# Sheet1.net
KiCad netlist of a schematic drawn in Altium Designer
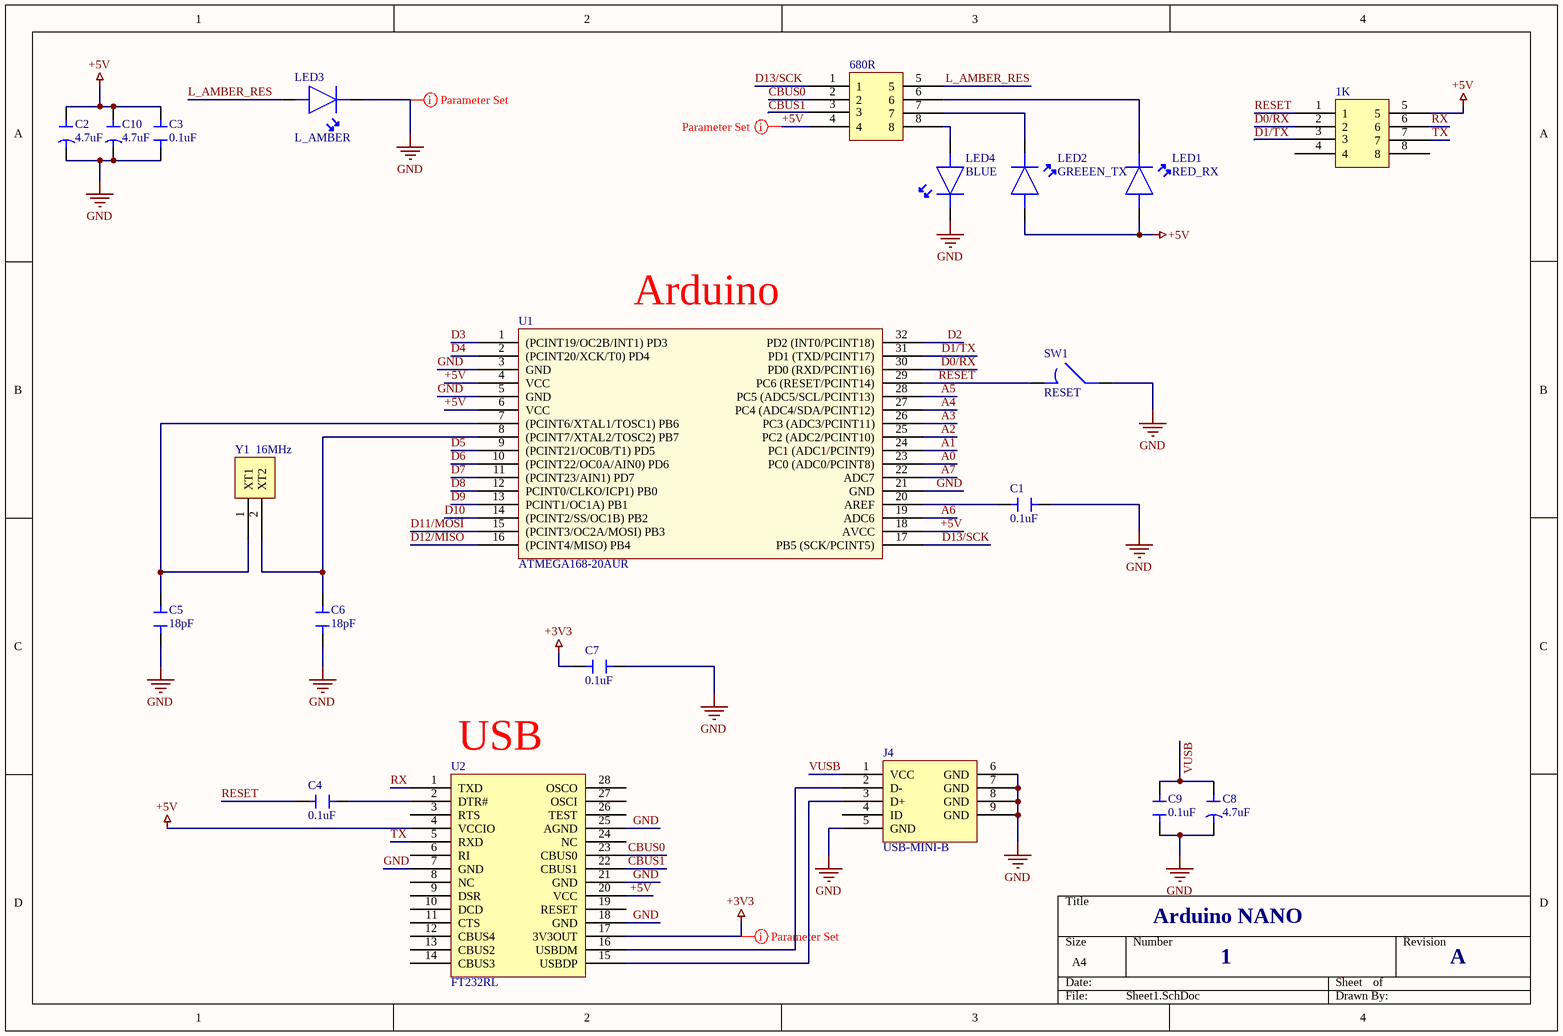
[diagram p0: Sheet1.SchDoc]

(export (version "E")
  (design (tool "Eeschema 10.0.6"))
  (components
    (comp (ref "1K")
      (value "YC164-JR-071KL")
      (footprint "Quad8 RES ARRAY")
      (description "Res Thick Film Array 1KOhm 5% 200ppm/C ISOL Epoxy 8-Pin 1206(4 X 0603) Convex SMD T/R")
      (fields (field (name "MANUFACTURER") "Yageo") (field (name "TOLERANCE") "5%"))
      (libsource (lib "Schlib1") (part "YC164-JR-071KL"))
    )
    (comp (ref "680R")
      (value "YC164-JR-07680RL")
      (footprint "Quad8 RES ARRAY")
      (description "Res Thick Film Array 680 Ohm 5% 200ppm/ C ISOL Molded 8-Pin 1206(4 X 0603) Convex SMD Paper T/R")
      (fields (field (name "MANUFACTURER") "Yageo"))
      (libsource (lib "Schlib1") (part "YC164-JR-07680RL"))
    )
    (comp (ref "C1")
      (value "0.1uF")
      (footprint "Capacitor 0805")
      (libsource (lib "Schlib1") (part "CL21F104ZBCNNNC"))
    )
    (comp (ref "C2")
      (value "4.7uF")
      (footprint "Tant 7343-43")
      (description "Cap Tant Solid 4.7uF 50V D CASE 10% (7.3 X 4.3 X 2.8mm) SMD 7343-31 1.2 Ohm 125 C T/R")
      (fields
        (field (name "MANUFACTURER") "Vishay Sprague")
        (field (name "MANUFACTURER PART NUMBER") "293D475X9050D2TE3")
      )
      (libsource (lib "Schlib1") (part "293D475X9050D2TE3"))
    )
    (comp (ref "C3")
      (value "0.1uF")
      (footprint "Capacitor 0805")
      (description "Multilayer Ceramic Capacitor, 18 pF, 16 V, ± 2%, C0G (NP0), 0805 [2012 Metric]")
      (fields
        (field (name "MANUFACTURER") "Vishay Vitramon")
        (field (name "MANUFACTURER PART NUMBER") "VJ0805A180GXJCW1BC")
      )
      (libsource (lib "Schlib1") (part "VJ0805A180GXJCW1BC"))
    )
    (comp (ref "C4")
      (value "0.1uF")
      (footprint "Capacitor 0805")
      (description "Multilayer Ceramic Capacitor, 18 pF, 16 V, ± 2%, C0G (NP0), 0805 [2012 Metric]")
      (fields
        (field (name "MANUFACTURER") "Vishay Vitramon")
        (field (name "MANUFACTURER PART NUMBER") "VJ0805A180GXJCW1BC")
      )
      (libsource (lib "Schlib1") (part "VJ0805A180GXJCW1BC"))
    )
    (comp (ref "C5")
      (value "18pF")
      (footprint "Capacitor 0805")
      (description "Multilayer Ceramic Capacitor, 18 pF, 16 V, ± 2%, C0G (NP0), 0805 [2012 Metric]")
      (fields
        (field (name "MANUFACTURER") "Vishay Vitramon")
        (field (name "MANUFACTURER PART NUMBER") "VJ0805A180GXJCW1BC")
      )
      (libsource (lib "Schlib1") (part "VJ0805A180GXJCW1BC"))
    )
    (comp (ref "C6")
      (value "18pF")
      (footprint "Capacitor 0805")
      (description "Multilayer Ceramic Capacitor, 18 pF, 16 V, ± 2%, C0G (NP0), 0805 [2012 Metric]")
      (fields
        (field (name "MANUFACTURER") "Vishay Vitramon")
        (field (name "MANUFACTURER PART NUMBER") "VJ0805A180GXJCW1BC")
      )
      (libsource (lib "Schlib1") (part "VJ0805A180GXJCW1BC"))
    )
    (comp (ref "C7")
      (value "0.1uF")
      (footprint "Capacitor 0805")
      (description "Multilayer Ceramic Capacitor, 18 pF, 16 V, ± 2%, C0G (NP0), 0805 [2012 Metric]")
      (fields
        (field (name "MANUFACTURER") "Vishay Vitramon")
        (field (name "MANUFACTURER PART NUMBER") "VJ0805A180GXJCW1BC")
      )
      (libsource (lib "Schlib1") (part "VJ0805A180GXJCW1BC"))
    )
    (comp (ref "C8")
      (value "4.7uF")
      (footprint "Tant 7343-43")
      (description "Cap Tant Solid 4.7uF 50V D CASE 10% (7.3 X 4.3 X 2.8mm) SMD 7343-31 1.2 Ohm 125 C T/R")
      (fields
        (field (name "MANUFACTURER") "Vishay Sprague")
        (field (name "MANUFACTURER PART NUMBER") "293D475X9050D2TE3")
      )
      (libsource (lib "Schlib1") (part "293D475X9050D2TE3"))
    )
    (comp (ref "C9")
      (value "0.1uF")
      (footprint "Capacitor 0805")
      (description "Multilayer Ceramic Capacitor, 18 pF, 16 V, ± 2%, C0G (NP0), 0805 [2012 Metric]")
      (fields
        (field (name "MANUFACTURER") "Vishay Vitramon")
        (field (name "MANUFACTURER PART NUMBER") "VJ0805A180GXJCW1BC")
      )
      (libsource (lib "Schlib1") (part "VJ0805A180GXJCW1BC"))
    )
    (comp (ref "C10")
      (value "4.7uF")
      (footprint "Tant 7343-43")
      (description "Cap Tant Solid 4.7uF 50V D CASE 10% (7.3 X 4.3 X 2.8mm) SMD 7343-31 1.2 Ohm 125 C T/R")
      (fields
        (field (name "MANUFACTURER") "Vishay Sprague")
        (field (name "MANUFACTURER PART NUMBER") "293D475X9050D2TE3")
      )
      (libsource (lib "Schlib1") (part "293D475X9050D2TE3"))
    )
    (comp (ref "J4")
      (value "USB-MINI-B")
      (footprint "Mini B")
      (description "Conn Mini USB 2.0 Type B RCP 5 POS 0.8mm Solder RA SMD 5 Terminal 1 Port USB OTG T/R")
      (fields (field (name "MANUFACTURER") "Molex") (field (name "MANUFACTURER PART NUMBER") "67503-1020"))
      (libsource (lib "Schlib1") (part "67503-1020"))
    )
    (comp (ref "LED1")
      (value "RED_RX")
      (footprint "LED 0805")
      (libsource (lib "Schlib1") (part "APT2012SRCPRV"))
    )
    (comp (ref "LED2")
      (value "GREEEN_TX")
      (footprint "LED 0805")
      (libsource (lib "Schlib1") (part "APT2012SRCPRV"))
    )
    (comp (ref "LED3")
      (value "L_AMBER")
      (footprint "LED 0805")
      (libsource (lib "Schlib1") (part "APT2012SRCPRV"))
    )
    (comp (ref "LED4")
      (value "BLUE")
      (footprint "LED 0805")
      (libsource (lib "Schlib1") (part "APT2012SRCPRV"))
    )
    (comp (ref "SW1")
      (value "RESET")
      (footprint "PUSH BUTTON")
      (description "Switch Tactile N.O. SPST Round Button Gull Wing 0.05A 12VDC 1.5N SMD Embossed T/R")
      (fields (field (name "MANUFACTURER") "Omron") (field (name "MANUFACTURER PART NUMBER") "B3U-1000P"))
      (libsource (lib "Schlib1") (part "B3U-1000P"))
    )
    (comp (ref "U1")
      (value "ATMEGA168-20AUR")
      (footprint "TQFP")
      (description "MCU 8-bit ATmega AVR RISC 16KB Flash 3.3V/5V 32-Pin TQFP T/R - Tape and Reel")
      (fields (field (name "MANUFACTURER") "Microchip"))
      (libsource (lib "Schlib1") (part "ATMEGA168-20AUR"))
    )
    (comp (ref "U2")
      (value "FT232RL")
      (footprint "Quad28 FTDI")
      (description "IC USB FS SERIAL UART 28-SSOP")
      (fields (field (name "MANUFACTURER") "FTDI") (field (name "MANUFACTURER PART NUMBER") "FT232RL-REEL"))
      (libsource (lib "Schlib1") (part "FT232RL-REEL"))
    )
    (comp (ref "Y1")
      (value "16MHz")
      (footprint "TH XT")
      (description "Crystal 16MHz ±20ppm (Tol) ±50ppm (Stability) 18pF FUND 40Ohm 2-Pin HC-49/US Thru-Hole Bulk")
      (fields
        (field (name "MANUFACTURER") "Abracon")
        (field (name "MANUFACTURER PART NUMBER") "ABL-16.000MHZ-B2")
      )
      (libsource (lib "Schlib1") (part "ABL-16.000MHZ-B2"))
    )
  )
  (nets
    (net (code "1") (name "+3V3") (class "Default")
      (node (ref "C7") (pin "2") (pinfunction "2_2") (pintype "passive"))
      (node (ref "U2") (pin "17") (pinfunction "3V3OUT_17") (pintype "passive"))
    )
    (net (code "2") (name "+5V") (class "Default")
      (node (ref "1K") (pin "5") (pinfunction "5_5") (pintype "passive"))
      (node (ref "680R") (pin "4") (pinfunction "4_4") (pintype "passive"))
      (node (ref "C10") (pin "1") (pinfunction "1_1") (pintype "passive"))
      (node (ref "C2") (pin "1") (pinfunction "1_1") (pintype "passive"))
      (node (ref "C3") (pin "1") (pinfunction "1_1") (pintype "passive"))
      (node (ref "LED1") (pin "8") (pinfunction "8_8") (pintype "passive"))
      (node (ref "LED2") (pin "8") (pinfunction "8_8") (pintype "passive"))
      (node (ref "U1") (pin "18") (pinfunction "AVCC_18") (pintype "passive"))
      (node (ref "U1") (pin "4") (pinfunction "VCC_4") (pintype "passive"))
      (node (ref "U1") (pin "6") (pinfunction "VCC_6") (pintype "passive"))
      (node (ref "U2") (pin "20") (pinfunction "VCC_20") (pintype "passive"))
      (node (ref "U2") (pin "4") (pinfunction "VCCIO_4") (pintype "passive"))
    )
    (net (code "3") (name "/A0") (class "Default")
      (node (ref "U1") (pin "23") (pinfunction "PC0_(ADC0/PCINT8)_23") (pintype "passive"))
    )
    (net (code "4") (name "/A1") (class "Default")
      (node (ref "U1") (pin "24") (pinfunction "PC1_(ADC1/PCINT9)_24") (pintype "passive"))
    )
    (net (code "5") (name "/A2") (class "Default")
      (node (ref "U1") (pin "25") (pinfunction "PC2_(ADC2/PCINT10)_25") (pintype "passive"))
    )
    (net (code "6") (name "/A3") (class "Default")
      (node (ref "U1") (pin "26") (pinfunction "PC3_(ADC3/PCINT11)_26") (pintype "passive"))
    )
    (net (code "7") (name "/A4") (class "Default")
      (node (ref "U1") (pin "27") (pinfunction "PC4_(ADC4/SDA/PCINT12)_27") (pintype "passive"))
    )
    (net (code "8") (name "/A5") (class "Default")
      (node (ref "U1") (pin "28") (pinfunction "PC5_(ADC5/SCL/PCINT13)_28") (pintype "passive"))
    )
    (net (code "9") (name "/A6") (class "Default")
      (node (ref "U1") (pin "19") (pinfunction "ADC6_19") (pintype "passive"))
    )
    (net (code "10") (name "/A7") (class "Default")
      (node (ref "U1") (pin "22") (pinfunction "ADC7_22") (pintype "passive"))
    )
    (net (code "11") (name "/CBUS0") (class "Default")
      (node (ref "680R") (pin "2") (pinfunction "2_2") (pintype "passive"))
      (node (ref "U2") (pin "23") (pinfunction "CBUS0_23") (pintype "passive"))
    )
    (net (code "12") (name "/CBUS1") (class "Default")
      (node (ref "680R") (pin "3") (pinfunction "3_3") (pintype "passive"))
      (node (ref "U2") (pin "22") (pinfunction "CBUS1_22") (pintype "passive"))
    )
    (net (code "13") (name "/D0{slash}RX") (class "Default")
      (node (ref "1K") (pin "2") (pinfunction "2_2") (pintype "passive"))
      (node (ref "U1") (pin "30") (pinfunction "PD0_(RXD/PCINT16)_30") (pintype "passive"))
    )
    (net (code "14") (name "/D1{slash}TX") (class "Default")
      (node (ref "1K") (pin "3") (pinfunction "3_3") (pintype "passive"))
      (node (ref "U1") (pin "31") (pinfunction "PD1_(TXD/PCINT17)_31") (pintype "passive"))
    )
    (net (code "15") (name "/D2") (class "Default")
      (node (ref "U1") (pin "32") (pinfunction "PD2_(INT0/PCINT18)_32") (pintype "passive"))
    )
    (net (code "16") (name "/D3") (class "Default")
      (node (ref "U1") (pin "1") (pinfunction "(PCINT19/OC2B/INT1)_PD3_1") (pintype "passive"))
    )
    (net (code "17") (name "/D4") (class "Default")
      (node (ref "U1") (pin "2") (pinfunction "(PCINT20/XCK/T0)_PD4_2") (pintype "passive"))
    )
    (net (code "18") (name "/D5") (class "Default")
      (node (ref "U1") (pin "9") (pinfunction "(PCINT21/OC0B/T1)_PD5_9") (pintype "passive"))
    )
    (net (code "19") (name "/D6") (class "Default")
      (node (ref "U1") (pin "10") (pinfunction "(PCINT22/OC0A/AIN0)_PD6_10") (pintype "passive"))
    )
    (net (code "20") (name "/D7") (class "Default")
      (node (ref "U1") (pin "11") (pinfunction "(PCINT23/AIN1)_PD7_11") (pintype "passive"))
    )
    (net (code "21") (name "/D8") (class "Default")
      (node (ref "U1") (pin "12") (pinfunction "PCINT0/CLKO/ICP1)_PB0_12") (pintype "passive"))
    )
    (net (code "22") (name "/D9") (class "Default")
      (node (ref "U1") (pin "13") (pinfunction "PCINT1/OC1A)_PB1_13") (pintype "passive"))
    )
    (net (code "23") (name "/D10") (class "Default")
      (node (ref "U1") (pin "14") (pinfunction "(PCINT2/SS/OC1B)_PB2_14") (pintype "passive"))
    )
    (net (code "24") (name "/D11{slash}MOSI") (class "Default")
      (node (ref "U1") (pin "15") (pinfunction "(PCINT3/OC2A/MOSI)_PB3_15") (pintype "passive"))
    )
    (net (code "25") (name "/D12{slash}MISO") (class "Default")
      (node (ref "U1") (pin "16") (pinfunction "(PCINT4/MISO)_PB4_16") (pintype "passive"))
    )
    (net (code "26") (name "/D13{slash}SCK") (class "Default")
      (node (ref "680R") (pin "1") (pinfunction "1_1") (pintype "passive"))
      (node (ref "U1") (pin "17") (pinfunction "PB5_(SCK/PCINT5)_17") (pintype "passive"))
    )
    (net (code "27") (name "/L_AMBER_RES") (class "Default")
      (node (ref "680R") (pin "5") (pinfunction "5_5") (pintype "passive"))
      (node (ref "LED3") (pin "8") (pinfunction "8_8") (pintype "passive"))
    )
    (net (code "28") (name "/RESET") (class "Default")
      (node (ref "1K") (pin "1") (pinfunction "1_1") (pintype "passive"))
      (node (ref "C4") (pin "2") (pinfunction "2_2") (pintype "passive"))
      (node (ref "SW1") (pin "9") (pinfunction "9_9") (pintype "passive"))
      (node (ref "U1") (pin "29") (pinfunction "PC6_(RESET/PCINT14)_29") (pintype "passive"))
    )
    (net (code "29") (name "/RX") (class "Default")
      (node (ref "1K") (pin "6") (pinfunction "6_6") (pintype "passive"))
      (node (ref "U2") (pin "1") (pinfunction "TXD_1") (pintype "passive"))
    )
    (net (code "30") (name "/TX") (class "Default")
      (node (ref "1K") (pin "7") (pinfunction "7_7") (pintype "passive"))
      (node (ref "U2") (pin "5") (pinfunction "RXD_5") (pintype "passive"))
    )
    (net (code "31") (name "/VUSB") (class "Default")
      (node (ref "C8") (pin "1") (pinfunction "1_1") (pintype "passive"))
      (node (ref "C9") (pin "1") (pinfunction "1_1") (pintype "passive"))
      (node (ref "J4") (pin "1") (pinfunction "VCC_1") (pintype "passive"))
    )
    (net (code "32") (name "GND") (class "Default")
      (node (ref "C1") (pin "2") (pinfunction "2_2") (pintype "passive"))
      (node (ref "C10") (pin "2") (pinfunction "2_2") (pintype "passive"))
      (node (ref "C2") (pin "2") (pinfunction "2_2") (pintype "passive"))
      (node (ref "C3") (pin "2") (pinfunction "2_2") (pintype "passive"))
      (node (ref "C5") (pin "1") (pinfunction "1_1") (pintype "passive"))
      (node (ref "C6") (pin "1") (pinfunction "1_1") (pintype "passive"))
      (node (ref "C7") (pin "1") (pinfunction "1_1") (pintype "passive"))
      (node (ref "C8") (pin "2") (pinfunction "2_2") (pintype "passive"))
      (node (ref "C9") (pin "2") (pinfunction "2_2") (pintype "passive"))
      (node (ref "J4") (pin "5") (pinfunction "GND_5") (pintype "passive"))
      (node (ref "J4") (pin "6") (pinfunction "GND_6") (pintype "passive"))
      (node (ref "J4") (pin "7") (pinfunction "GND_7") (pintype "passive"))
      (node (ref "J4") (pin "8") (pinfunction "GND_8") (pintype "passive"))
      (node (ref "J4") (pin "9") (pinfunction "GND_9") (pintype "passive"))
      (node (ref "LED3") (pin "7") (pinfunction "7_7") (pintype "passive"))
      (node (ref "LED4") (pin "7") (pinfunction "7_7") (pintype "passive"))
      (node (ref "SW1") (pin "10") (pinfunction "10_10") (pintype "passive"))
      (node (ref "U1") (pin "21") (pinfunction "GND_21") (pintype "passive"))
      (node (ref "U1") (pin "3") (pinfunction "GND_3") (pintype "passive"))
      (node (ref "U1") (pin "5") (pinfunction "GND_5") (pintype "passive"))
      (node (ref "U2") (pin "18") (pinfunction "GND_18") (pintype "passive"))
      (node (ref "U2") (pin "21") (pinfunction "GND_21") (pintype "passive"))
      (node (ref "U2") (pin "25") (pinfunction "AGND_25") (pintype "passive"))
      (node (ref "U2") (pin "7") (pinfunction "GND_7") (pintype "passive"))
    )
    (net (code "33") (name "Net-(680R-Pad6)") (class "Default")
      (node (ref "680R") (pin "6") (pinfunction "6_6") (pintype "passive"))
      (node (ref "LED1") (pin "7") (pinfunction "7_7") (pintype "passive"))
    )
    (net (code "34") (name "Net-(680R-Pad7)") (class "Default")
      (node (ref "680R") (pin "7") (pinfunction "7_7") (pintype "passive"))
      (node (ref "LED2") (pin "7") (pinfunction "7_7") (pintype "passive"))
    )
    (net (code "35") (name "Net-(680R-Pad8)") (class "Default")
      (node (ref "680R") (pin "8") (pinfunction "8_8") (pintype "passive"))
      (node (ref "LED4") (pin "8") (pinfunction "8_8") (pintype "passive"))
    )
    (net (code "36") (name "Net-(J4-D+)") (class "Default")
      (node (ref "J4") (pin "3") (pinfunction "D+_3") (pintype "passive"))
      (node (ref "U2") (pin "15") (pinfunction "USBDP_15") (pintype "passive"))
    )
    (net (code "37") (name "Net-(J4-D-)") (class "Default")
      (node (ref "J4") (pin "2") (pinfunction "D-_2") (pintype "passive"))
      (node (ref "U2") (pin "16") (pinfunction "USBDM_16") (pintype "passive"))
    )
    (net (code "38") (name "Net-(U1-(PCINT6{slash}XTAL1{slash}TOSC1)_PB6)") (class "Default")
      (node (ref "C5") (pin "2") (pinfunction "2_2") (pintype "passive"))
      (node (ref "U1") (pin "7") (pinfunction "(PCINT6/XTAL1/TOSC1)_PB6_7") (pintype "passive"))
      (node (ref "Y1") (pin "1") (pinfunction "XT1_1") (pintype "passive"))
    )
    (net (code "39") (name "Net-(U1-(PCINT7{slash}XTAL2{slash}TOSC2)_PB7)") (class "Default")
      (node (ref "C6") (pin "2") (pinfunction "2_2") (pintype "passive"))
      (node (ref "U1") (pin "8") (pinfunction "(PCINT7/XTAL2/TOSC2)_PB7_8") (pintype "passive"))
      (node (ref "Y1") (pin "2") (pinfunction "XT2_2") (pintype "passive"))
    )
    (net (code "40") (name "Net-(U1-AREF)") (class "Default")
      (node (ref "C1") (pin "1") (pinfunction "1_1") (pintype "passive"))
      (node (ref "U1") (pin "20") (pinfunction "AREF_20") (pintype "passive"))
    )
    (net (code "41") (name "Net-(U2-DTR#)") (class "Default")
      (node (ref "C4") (pin "1") (pinfunction "1_1") (pintype "passive"))
      (node (ref "U2") (pin "2") (pinfunction "DTR#_2") (pintype "passive"))
    )
    (net (code "42") (name "unconnected-(1K-Pad4)") (class "Default")
      (node (ref "1K") (pin "4") (pinfunction "4_4") (pintype "passive"))
    )
    (net (code "43") (name "unconnected-(1K-Pad8)") (class "Default")
      (node (ref "1K") (pin "8") (pinfunction "8_8") (pintype "passive"))
    )
    (net (code "44") (name "unconnected-(J4-ID-Pad4)") (class "Default")
      (node (ref "J4") (pin "4") (pinfunction "ID_4") (pintype "passive"))
    )
    (net (code "45") (name "unconnected-(U2-CBUS2-Pad13)") (class "Default")
      (node (ref "U2") (pin "13") (pinfunction "CBUS2_13") (pintype "passive"))
    )
    (net (code "46") (name "unconnected-(U2-CBUS3-Pad14)") (class "Default")
      (node (ref "U2") (pin "14") (pinfunction "CBUS3_14") (pintype "passive"))
    )
    (net (code "47") (name "unconnected-(U2-CBUS4-Pad12)") (class "Default")
      (node (ref "U2") (pin "12") (pinfunction "CBUS4_12") (pintype "passive"))
    )
    (net (code "48") (name "unconnected-(U2-CTS-Pad11)") (class "Default")
      (node (ref "U2") (pin "11") (pinfunction "CTS_11") (pintype "passive"))
    )
    (net (code "49") (name "unconnected-(U2-DCD-Pad10)") (class "Default")
      (node (ref "U2") (pin "10") (pinfunction "DCD_10") (pintype "passive"))
    )
    (net (code "50") (name "unconnected-(U2-DSR-Pad9)") (class "Default")
      (node (ref "U2") (pin "9") (pinfunction "DSR_9") (pintype "passive"))
    )
    (net (code "51") (name "unconnected-(U2-NC-Pad8)") (class "Default")
      (node (ref "U2") (pin "8") (pinfunction "NC_8") (pintype "passive"))
    )
    (net (code "52") (name "unconnected-(U2-NC-Pad24)") (class "Default")
      (node (ref "U2") (pin "24") (pinfunction "NC_24") (pintype "passive"))
    )
    (net (code "53") (name "unconnected-(U2-OSCI-Pad27)") (class "Default")
      (node (ref "U2") (pin "27") (pinfunction "OSCI_27") (pintype "passive"))
    )
    (net (code "54") (name "unconnected-(U2-OSCO-Pad28)") (class "Default")
      (node (ref "U2") (pin "28") (pinfunction "OSCO_28") (pintype "passive"))
    )
    (net (code "55") (name "unconnected-(U2-RESET-Pad19)") (class "Default")
      (node (ref "U2") (pin "19") (pinfunction "RESET_19") (pintype "passive"))
    )
    (net (code "56") (name "unconnected-(U2-RI-Pad6)") (class "Default")
      (node (ref "U2") (pin "6") (pinfunction "RI_6") (pintype "passive"))
    )
    (net (code "57") (name "unconnected-(U2-RTS-Pad3)") (class "Default")
      (node (ref "U2") (pin "3") (pinfunction "RTS_3") (pintype "passive"))
    )
    (net (code "58") (name "unconnected-(U2-TEST-Pad26)") (class "Default")
      (node (ref "U2") (pin "26") (pinfunction "TEST_26") (pintype "passive"))
    )
  )
)
